# H38R00.net
KiCad netlist of a schematic drawn in EAGLE
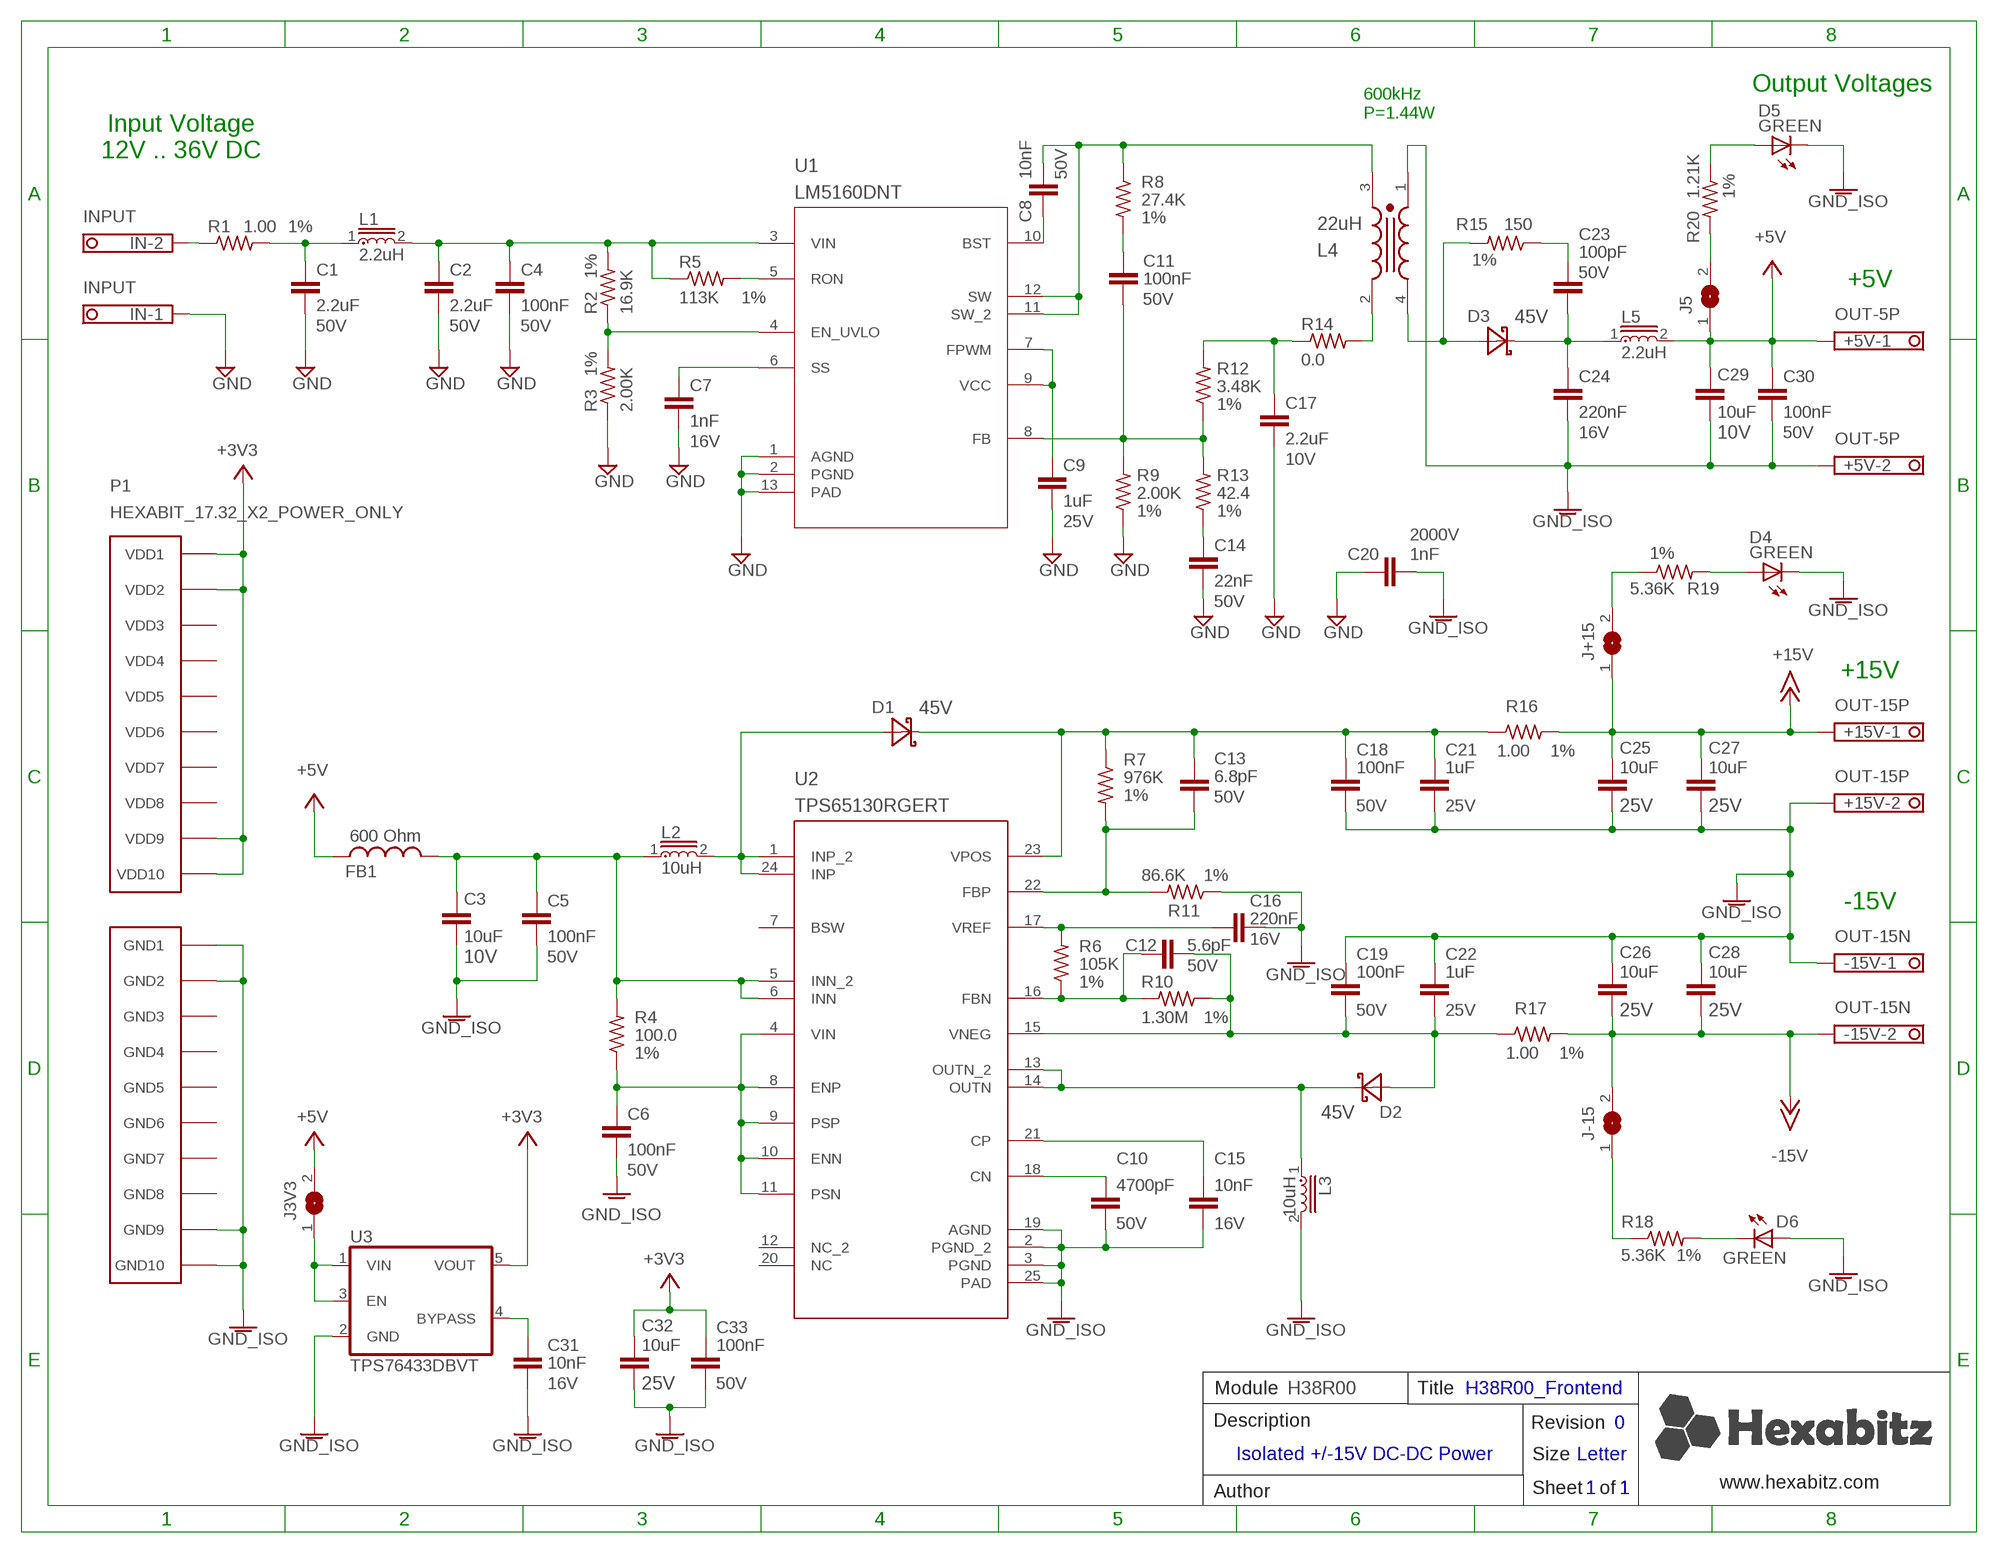
[diagram p0: schematic, sheet 1]

(export (version "E")
  (design (tool "Eeschema 10.0.6"))
  (components
    (comp (ref "+5V")
      (value "OUT-5P")
      (footprint "eagle-import:CON-PHOENIX-350_1751248")
      (fields (field (name "MPN") "1751251"))
      (libsource (lib "eagle-import") (part "CON-PHOENIX-350_1751248"))
    )
    (comp (ref "+15V")
      (value "OUT-15P")
      (footprint "eagle-import:CON-PHOENIX-350_1751248")
      (fields (field (name "MPN") "1751251"))
      (libsource (lib "eagle-import") (part "CON-PHOENIX-350_1751248"))
    )
    (comp (ref "-15V")
      (value "OUT-15N")
      (footprint "eagle-import:CON-PHOENIX-350_1751248")
      (fields (field (name "MPN") "1751251"))
      (libsource (lib "eagle-import") (part "CON-PHOENIX-350_1751248"))
    )
    (comp (ref "C1")
      (value "2.2uF")
      (footprint "eagle-import:C1206K")
      (fields (field (name "MPN") "UMK316B7225KD-T") (field (name "VOLTAGE") "50V"))
      (libsource (lib "eagle-import") (part "C-1206"))
    )
    (comp (ref "C2")
      (value "2.2uF")
      (footprint "eagle-import:C1206K")
      (fields (field (name "MPN") "UMK316B7225KD-T") (field (name "VOLTAGE") "50V"))
      (libsource (lib "eagle-import") (part "C-1206"))
    )
    (comp (ref "C3")
      (value "10uF")
      (footprint "eagle-import:C-0805")
      (fields
        (field (name "CAPACITANCE") "10uF")
        (field (name "MFN") "Würth Elektronik")
        (field (name "MPN") "885012207026")
        (field (name "OCTOPART_URL") "https://octopart.com/885012207026-w%C3%BCrth+elektronik-65419800?r=sp&s=PJ8-ZxRrRL-RXf1D2e7V7w ")
        (field (name "TOLERANCE") "10%")
        (field (name "VOLTAGE_RATING") "10V")
      )
      (libsource (lib "eagle-import") (part "C-0805"))
    )
    (comp (ref "C4")
      (value "100nF")
      (footprint "eagle-import:C-0603")
      (fields
        (field (name "CAPACITANCE") "100nF")
        (field (name "MFN") "TDK")
        (field (name "MPN") "C1608X7R1H104K")
        (field (name "OCTOPART_URL") "https://octopart.com/c1608x7r1h104k080aa-tdk-25947665?r=sp&s=vJ3_28x5RGekN18MBHqpKw")
        (field (name "TOLERANCE") "10%")
        (field (name "VOLTAGE_RATING") "50V")
      )
      (libsource (lib "eagle-import") (part "C-0603"))
    )
    (comp (ref "C5")
      (value "100nF")
      (footprint "eagle-import:C-0603")
      (fields
        (field (name "CAPACITANCE") "100nF")
        (field (name "MFN") "TDK")
        (field (name "MPN") "C1608X7R1H104K")
        (field (name "OCTOPART_URL") "https://octopart.com/c1608x7r1h104k080aa-tdk-25947665?r=sp&s=vJ3_28x5RGekN18MBHqpKw")
        (field (name "TOLERANCE") "10%")
        (field (name "VOLTAGE_RATING") "50V")
      )
      (libsource (lib "eagle-import") (part "C-0603"))
    )
    (comp (ref "C6")
      (value "100nF")
      (footprint "eagle-import:C-0603")
      (fields
        (field (name "CAPACITANCE") "100nF")
        (field (name "MFN") "TDK")
        (field (name "MPN") "C1608X7R1H104K")
        (field (name "OCTOPART_URL") "https://octopart.com/c1608x7r1h104k080aa-tdk-25947665?r=sp&s=vJ3_28x5RGekN18MBHqpKw")
        (field (name "TOLERANCE") "10%")
        (field (name "VOLTAGE_RATING") "50V")
      )
      (libsource (lib "eagle-import") (part "C-0603"))
    )
    (comp (ref "C7")
      (value "1nF")
      (footprint "eagle-import:C-0603")
      (fields
        (field (name "CAPACITANCE") "1nF")
        (field (name "MFN") "Würth Elektronik")
        (field (name "MPN") "885012206034")
        (field (name "OCTOPART_URL") "https://octopart.com/885012206034-w%C3%BCrth+elektronik-53914743?r=sp&s=3y92xzxLSKK6IudBxcGU8w")
        (field (name "TOLERANCE") "10%")
        (field (name "VOLTAGE_RATING") "16V")
      )
      (libsource (lib "eagle-import") (part "C-0603"))
    )
    (comp (ref "C8")
      (value "10nF")
      (footprint "eagle-import:C-0603")
      (fields
        (field (name "CAPACITANCE") "10nF")
        (field (name "MFN") "KEMET")
        (field (name "MPN") "C0603C103J5RACTU")
        (field (name "OCTOPART_URL") "https://octopart.com/c0603c103j5ractu-kemet-91371?r=sp&s=Kyc2xDn-SuWGmNLJldLSIQ")
        (field (name "TOLERANCE") "10%")
        (field (name "VOLTAGE_RATING") "50V")
      )
      (libsource (lib "eagle-import") (part "C-0603"))
    )
    (comp (ref "C9")
      (value "1uF")
      (footprint "eagle-import:C-0603")
      (fields
        (field (name "CAPACITANCE") "1uF")
        (field (name "MFN") "Taiyo Yuden")
        (field (name "MPN") "TMK107B7105KA-T")
        (field (name "OCTOPART_URL") "https://octopart.com/tmk107b7105ka-t-taiyo+yuden-20363789?r=sp&s=C0MvDSixSxq0oU7K_M5ppQ")
        (field (name "TOLERANCE") "10%")
        (field (name "VOLTAGE_RATING") "25V")
      )
      (libsource (lib "eagle-import") (part "C-0603"))
    )
    (comp (ref "C10")
      (value "4700pF")
      (footprint "eagle-import:C-0603")
      (fields
        (field (name "CAPACITANCE") "4700pF")
        (field (name "MFN") "Würth Elektronik")
        (field (name "MPN") "885012206087")
        (field (name "OCTOPART_URL") "https://octopart.com/885012206087-w%C3%BCrth+elektronik-53914796?r=sp&s=1K2nhhCgSUq-KN0bvB69Uw")
        (field (name "TOLERANCE") "10%")
        (field (name "VOLTAGE_RATING") "50V")
      )
      (libsource (lib "eagle-import") (part "C-0603"))
    )
    (comp (ref "C11")
      (value "100nF")
      (footprint "eagle-import:C-0603")
      (fields
        (field (name "CAPACITANCE") "100nF")
        (field (name "MFN") "TDK")
        (field (name "MPN") "C1608X7R1H104K")
        (field (name "OCTOPART_URL") "https://octopart.com/c1608x7r1h104k080aa-tdk-25947665?r=sp&s=vJ3_28x5RGekN18MBHqpKw")
        (field (name "TOLERANCE") "10%")
        (field (name "VOLTAGE_RATING") "50V")
      )
      (libsource (lib "eagle-import") (part "C-0603"))
    )
    (comp (ref "C12")
      (value "5.6pF")
      (footprint "eagle-import:C-0603")
      (fields
        (field (name "CAPACITANCE") "5.6pF")
        (field (name "MFN") "TDK")
        (field (name "MPN") "06035A5R6CAT2A")
        (field (name "OCTOPART_URL") "https://octopart.com/06035a5r6cat2a-avx-194782?r=sp&s=arSRmqwrS2KePu_erVaGmg")
        (field (name "TOLERANCE") "5%")
        (field (name "VOLTAGE_RATING") "50V")
      )
      (libsource (lib "eagle-import") (part "C-0603"))
    )
    (comp (ref "C13")
      (value "6.8pF")
      (footprint "eagle-import:C-0603")
      (fields
        (field (name "CAPACITANCE") "6.8pF")
        (field (name "MFN") "AVX")
        (field (name "MPN") "06035A6R8CAT2A")
        (field (name "OCTOPART_URL") "https://octopart.com/06035a6r8cat2a-avx-194783?r=sp&s=5-5NBtM6RDWLTSW9K30eVg")
        (field (name "TOLERANCE") "10%")
        (field (name "VOLTAGE_RATING") "50V")
      )
      (libsource (lib "eagle-import") (part "C-0603"))
    )
    (comp (ref "C14")
      (value "22nF")
      (footprint "eagle-import:C-0603")
      (fields
        (field (name "CAPACITANCE") "22nF")
        (field (name "MFN") "Murata")
        (field (name "MPN") "GRM188R71H223KA01D")
        (field (name "OCTOPART_URL") "https://octopart.com/grm188r71h223ka01d-murata-196232?r=sp&s=t23e6pi9S5yo9EHFMT_EKg")
        (field (name "TOLERANCE") "10%")
        (field (name "VOLTAGE_RATING") "50V")
      )
      (libsource (lib "eagle-import") (part "C-0603"))
    )
    (comp (ref "C15")
      (value "10nF")
      (footprint "eagle-import:C-0603")
      (fields
        (field (name "CAPACITANCE") "10nF")
        (field (name "MFN") "Würth Elektronik")
        (field (name "MPN") "885012206040")
        (field (name "OCTOPART_URL") "https://octopart.com/885012206040-w%C3%BCrth+elektronik-53914749?r=sp&s=G3_ezLbARM2-FohtMFECqg")
        (field (name "TOLERANCE") "10%")
        (field (name "VOLTAGE_RATING") "16V")
      )
      (libsource (lib "eagle-import") (part "C-0603"))
    )
    (comp (ref "C16")
      (value "220nF")
      (footprint "eagle-import:C-0603")
      (fields
        (field (name "CAPACITANCE") "220nF")
        (field (name "MFN") "Würth Elektronik")
        (field (name "MPN") "885012206048")
        (field (name "OCTOPART_URL") "https://octopart.com/885012206048-w%C3%BCrth+elektronik-53914757?r=sp&s=r2jVh1M7TTWSNtdrsMd35A")
        (field (name "TOLERANCE") "10%")
        (field (name "VOLTAGE_RATING") "16V")
      )
      (libsource (lib "eagle-import") (part "C-0603"))
    )
    (comp (ref "C17")
      (value "2.2uF")
      (footprint "eagle-import:C-0603")
      (fields
        (field (name "CAPACITANCE") "2.2uF")
        (field (name "MFN") "Murata")
        (field (name "MPN") "GRM188R71A225KE15D")
        (field (name "OCTOPART_URL") "https://octopart.com/grm188r71a225ke15d-murata-197889?r=sp&s=UhC5vs9xSQGkDEPPXrg6Ig")
        (field (name "TOLERANCE") "10%")
        (field (name "VOLTAGE_RATING") "10V")
      )
      (libsource (lib "eagle-import") (part "C-0603"))
    )
    (comp (ref "C18")
      (value "100nF")
      (footprint "eagle-import:C-0603")
      (fields
        (field (name "CAPACITANCE") "100nF")
        (field (name "MFN") "TDK")
        (field (name "MPN") "C1608X7R1H104K")
        (field (name "OCTOPART_URL") "https://octopart.com/c1608x7r1h104k080aa-tdk-25947665?r=sp&s=vJ3_28x5RGekN18MBHqpKw")
        (field (name "TOLERANCE") "10%")
        (field (name "VOLTAGE_RATING") "50V")
      )
      (libsource (lib "eagle-import") (part "C-0603"))
    )
    (comp (ref "C19")
      (value "100nF")
      (footprint "eagle-import:C-0603")
      (fields
        (field (name "CAPACITANCE") "100nF")
        (field (name "MFN") "TDK")
        (field (name "MPN") "C1608X7R1H104K")
        (field (name "OCTOPART_URL") "https://octopart.com/c1608x7r1h104k080aa-tdk-25947665?r=sp&s=vJ3_28x5RGekN18MBHqpKw")
        (field (name "TOLERANCE") "10%")
        (field (name "VOLTAGE_RATING") "50V")
      )
      (libsource (lib "eagle-import") (part "C-0603"))
    )
    (comp (ref "C20")
      (value "1nF")
      (footprint "eagle-import:C1206K")
      (fields (field (name "MPN") "202R18W102KV4E") (field (name "VOLTAGE") "2000V"))
      (libsource (lib "eagle-import") (part "C-1206"))
    )
    (comp (ref "C21")
      (value "1uF")
      (footprint "eagle-import:C-0603")
      (fields
        (field (name "CAPACITANCE") "1uF")
        (field (name "MFN") "Taiyo Yuden")
        (field (name "MPN") "TMK107B7105KA-T")
        (field (name "OCTOPART_URL") "https://octopart.com/tmk107b7105ka-t-taiyo+yuden-20363789?r=sp&s=C0MvDSixSxq0oU7K_M5ppQ")
        (field (name "TOLERANCE") "10%")
        (field (name "VOLTAGE_RATING") "25V")
      )
      (libsource (lib "eagle-import") (part "C-0603"))
    )
    (comp (ref "C22")
      (value "1uF")
      (footprint "eagle-import:C-0603")
      (fields
        (field (name "CAPACITANCE") "1uF")
        (field (name "MFN") "Taiyo Yuden")
        (field (name "MPN") "TMK107B7105KA-T")
        (field (name "OCTOPART_URL") "https://octopart.com/tmk107b7105ka-t-taiyo+yuden-20363789?r=sp&s=C0MvDSixSxq0oU7K_M5ppQ")
        (field (name "TOLERANCE") "10%")
        (field (name "VOLTAGE_RATING") "25V")
      )
      (libsource (lib "eagle-import") (part "C-0603"))
    )
    (comp (ref "C23")
      (value "100pF")
      (footprint "eagle-import:C-0603")
      (fields
        (field (name "CAPACITANCE") "100pF")
        (field (name "MFN") "KEMET")
        (field (name "MPN") "C0603C101J5GACTU")
        (field (name "OCTOPART_URL") "https://octopart.com/c0603c101j5gactu-kemet-100052?r=sp&s=G9Wafbc2Rs-t41DcITu08w")
        (field (name "TOLERANCE") "5%")
        (field (name "VOLTAGE_RATING") "50V")
      )
      (libsource (lib "eagle-import") (part "C-0603"))
    )
    (comp (ref "C24")
      (value "220nF")
      (footprint "eagle-import:C-0603")
      (fields
        (field (name "CAPACITANCE") "220nF")
        (field (name "MFN") "Würth Elektronik")
        (field (name "MPN") "885012206048")
        (field (name "OCTOPART_URL") "https://octopart.com/885012206048-w%C3%BCrth+elektronik-53914757?r=sp&s=r2jVh1M7TTWSNtdrsMd35A")
        (field (name "TOLERANCE") "10%")
        (field (name "VOLTAGE_RATING") "16V")
      )
      (libsource (lib "eagle-import") (part "C-0603"))
    )
    (comp (ref "C25")
      (value "10uF")
      (footprint "eagle-import:C-0805")
      (fields
        (field (name "CAPACITANCE") "10uF")
        (field (name "MFN") "Murata")
        (field (name "MPN") "GRM21BC71E106KE11L")
        (field (name "OCTOPART_URL") "https://octopart.com/grm21bc71e106ke11l-murata-51454492?r=sp&s=2Vde2RpCRyqy5YYMvYke3Q ")
        (field (name "TOLERANCE") "10%")
        (field (name "VOLTAGE_RATING") "25V")
      )
      (libsource (lib "eagle-import") (part "C-0805"))
    )
    (comp (ref "C26")
      (value "10uF")
      (footprint "eagle-import:C-0805")
      (fields
        (field (name "CAPACITANCE") "10uF")
        (field (name "MFN") "Murata")
        (field (name "MPN") "GRM21BC71E106KE11L")
        (field (name "OCTOPART_URL") "https://octopart.com/grm21bc71e106ke11l-murata-51454492?r=sp&s=2Vde2RpCRyqy5YYMvYke3Q ")
        (field (name "TOLERANCE") "10%")
        (field (name "VOLTAGE_RATING") "25V")
      )
      (libsource (lib "eagle-import") (part "C-0805"))
    )
    (comp (ref "C27")
      (value "10uF")
      (footprint "eagle-import:C-0805")
      (fields
        (field (name "CAPACITANCE") "10uF")
        (field (name "MFN") "Murata")
        (field (name "MPN") "GRM21BC71E106KE11L")
        (field (name "OCTOPART_URL") "https://octopart.com/grm21bc71e106ke11l-murata-51454492?r=sp&s=2Vde2RpCRyqy5YYMvYke3Q ")
        (field (name "TOLERANCE") "10%")
        (field (name "VOLTAGE_RATING") "25V")
      )
      (libsource (lib "eagle-import") (part "C-0805"))
    )
    (comp (ref "C28")
      (value "10uF")
      (footprint "eagle-import:C-0805")
      (fields
        (field (name "CAPACITANCE") "10uF")
        (field (name "MFN") "Murata")
        (field (name "MPN") "GRM21BC71E106KE11L")
        (field (name "OCTOPART_URL") "https://octopart.com/grm21bc71e106ke11l-murata-51454492?r=sp&s=2Vde2RpCRyqy5YYMvYke3Q")
        (field (name "TOLERANCE") "10%")
        (field (name "VOLTAGE_RATING") "25V")
      )
      (libsource (lib "eagle-import") (part "C-0805"))
    )
    (comp (ref "C29")
      (value "10uF")
      (footprint "eagle-import:C-0805")
      (fields
        (field (name "CAPACITANCE") "10uF")
        (field (name "MFN") "Würth Elektronik")
        (field (name "MPN") "885012207026")
        (field (name "OCTOPART_URL") "https://octopart.com/885012207026-w%C3%BCrth+elektronik-65419800?r=sp&s=PJ8-ZxRrRL-RXf1D2e7V7w")
        (field (name "TOLERANCE") "10%")
        (field (name "VOLTAGE_RATING") "10V")
      )
      (libsource (lib "eagle-import") (part "C-0805"))
    )
    (comp (ref "C30")
      (value "100nF")
      (footprint "eagle-import:C-0603")
      (fields
        (field (name "CAPACITANCE") "100nF")
        (field (name "MFN") "TDK")
        (field (name "MPN") "C1608X7R1H104K")
        (field (name "OCTOPART_URL") "https://octopart.com/c1608x7r1h104k080aa-tdk-25947665?r=sp&s=vJ3_28x5RGekN18MBHqpKw")
        (field (name "TOLERANCE") "10%")
        (field (name "VOLTAGE_RATING") "50V")
      )
      (libsource (lib "eagle-import") (part "C-0603"))
    )
    (comp (ref "C31")
      (value "10nF")
      (footprint "eagle-import:C-0603")
      (fields
        (field (name "CAPACITANCE") "10nF")
        (field (name "MFN") "Würth Elektronik")
        (field (name "MPN") "885012206040")
        (field (name "OCTOPART_URL") "https://octopart.com/885012206040-w%C3%BCrth+elektronik-53914749?r=sp&s=G3_ezLbARM2-FohtMFECqg")
        (field (name "TOLERANCE") "10%")
        (field (name "VOLTAGE_RATING") "16V")
      )
      (libsource (lib "eagle-import") (part "C-0603"))
    )
    (comp (ref "C32")
      (value "10uF")
      (footprint "eagle-import:C-0805")
      (fields
        (field (name "CAPACITANCE") "10uF")
        (field (name "MFN") "Murata")
        (field (name "MPN") "GRM21BC71E106KE11L")
        (field (name "OCTOPART_URL") "https://octopart.com/grm21bc71e106ke11l-murata-51454492?r=sp&s=2Vde2RpCRyqy5YYMvYke3Q")
        (field (name "TOLERANCE") "10%")
        (field (name "VOLTAGE_RATING") "25V")
      )
      (libsource (lib "eagle-import") (part "C-0805"))
    )
    (comp (ref "C33")
      (value "100nF")
      (footprint "eagle-import:C-0603")
      (fields
        (field (name "CAPACITANCE") "100nF")
        (field (name "MFN") "TDK")
        (field (name "MPN") "C1608X7R1H104K")
        (field (name "OCTOPART_URL") "https://octopart.com/c1608x7r1h104k080aa-tdk-25947665?r=sp&s=vJ3_28x5RGekN18MBHqpKw")
        (field (name "TOLERANCE") "10%")
        (field (name "VOLTAGE_RATING") "50V")
      )
      (libsource (lib "eagle-import") (part "C-0603"))
    )
    (comp (ref "D1")
      (value "DIOD-SOD-123")
      (footprint "eagle-import:SOD123")
      (fields
        (field (name "MFN") "ON Semiconductor")
        (field (name "MPN") "NTS245SFT1G")
        (field (name "OCTOPART_URL") "https://octopart.com/nts245sft1g-on+semiconductor-53638116?r=sp&s=Zo8Z59f0QcynsgZ2PtBRwg")
        (field (name "VOLTAGE_RATING_DC") "45V")
      )
      (libsource (lib "eagle-import") (part "DIOD-SOD-123"))
    )
    (comp (ref "D2")
      (value "DIOD-SOD-123")
      (footprint "eagle-import:SOD123")
      (fields
        (field (name "MFN") "ON Semiconductor")
        (field (name "MPN") "NTS245SFT1G")
        (field (name "OCTOPART_URL") "https://octopart.com/nts245sft1g-on+semiconductor-53638116?r=sp&s=Zo8Z59f0QcynsgZ2PtBRwg")
        (field (name "VOLTAGE_RATING_DC") "45V")
      )
      (libsource (lib "eagle-import") (part "DIOD-SOD-123"))
    )
    (comp (ref "D3")
      (value "DIOD-SOD-123")
      (footprint "eagle-import:SOD123")
      (fields
        (field (name "MFN") "ON Semiconductor")
        (field (name "MPN") "NTS245SFT1G")
        (field (name "OCTOPART_URL") "https://octopart.com/nts245sft1g-on+semiconductor-53638116?r=sp&s=Zo8Z59f0QcynsgZ2PtBRwg")
        (field (name "VOLTAGE_RATING_DC") "45V")
      )
      (libsource (lib "eagle-import") (part "DIOD-SOD-123"))
    )
    (comp (ref "D4")
      (value "GREEN")
      (footprint "eagle-import:VLMS1300-GS08")
      (fields (field (name "MPN") "VLMTG1300-GS08"))
      (libsource (lib "eagle-import") (part "VLMTG1300-GS08"))
    )
    (comp (ref "D5")
      (value "GREEN")
      (footprint "eagle-import:VLMS1300-GS08")
      (fields (field (name "MPN") "VLMTG1300-GS08"))
      (libsource (lib "eagle-import") (part "VLMTG1300-GS08"))
    )
    (comp (ref "D6")
      (value "GREEN")
      (footprint "eagle-import:VLMS1300-GS08")
      (fields (field (name "MPN") "VLMTG1300-GS08"))
      (libsource (lib "eagle-import") (part "VLMTG1300-GS08"))
    )
    (comp (ref "FB1")
      (value "600 Ohm")
      (footprint "eagle-import:FB-0603")
      (fields
        (field (name "MFN") "Murata")
        (field (name "MPN") "BLM18KG601SN1D")
        (field (name "OCTOPART_URL") "https://octopart.com/blm18kg601sn1d-murata-12276433?r=sp&s=hc41AUOpRWisdZqqWWZOxA")
      )
      (libsource (lib "eagle-import") (part "FB-0603"))
    )
    (comp (ref "IN")
      (value "INPUT")
      (footprint "eagle-import:CON-PHOENIX-350_1751248")
      (fields (field (name "MPN") "1751251"))
      (libsource (lib "eagle-import") (part "CON-PHOENIX-350_1751248"))
    )
    (comp (ref "J+15")
      (value "SJ")
      (footprint "eagle-import:SJ")
      (libsource (lib "eagle-import") (part "SJ"))
    )
    (comp (ref "J-15")
      (value "SJ")
      (footprint "eagle-import:SJ")
      (libsource (lib "eagle-import") (part "SJ"))
    )
    (comp (ref "J3V3")
      (value "SJ")
      (footprint "eagle-import:SJ")
      (libsource (lib "eagle-import") (part "SJ"))
    )
    (comp (ref "J5") (value "SJ") (footprint "eagle-import:SJ") (libsource (lib "eagle-import") (part "SJ")))
    (comp (ref "L1")
      (value "2.2uH")
      (footprint "eagle-import:C-0603")
      (fields (field (name "MPN") "LQM18PN2R2MFHD"))
      (libsource (lib "eagle-import") (part "LQM18PN2R2MFHD"))
    )
    (comp (ref "L2")
      (value "10uH")
      (footprint "eagle-import:WUERTH_ELEKTRONIK_74404024100_0")
      (fields (field (name "MF") "Wuerth Elektronik") (field (name "MPN") "74404024100"))
      (libsource (lib "eagle-import") (part "WUERTH_ELEKTRONIK_74404024100WUERTH_ELEKTRONIK_74404024100_0_0"))
    )
    (comp (ref "L3")
      (value "10uH")
      (footprint "eagle-import:WUERTH_ELEKTRONIK_74404024100_0")
      (fields (field (name "MF") "Wuerth Elektronik") (field (name "MPN") "74404024100"))
      (libsource (lib "eagle-import") (part "WUERTH_ELEKTRONIK_74404024100WUERTH_ELEKTRONIK_74404024100_0_0"))
    )
    (comp (ref "L4")
      (value "22uH")
      (footprint "eagle-import:WUERTH_ELEKTRONIK_74489430220_0")
      (fields (field (name "MF") "Wuerth Elektronik") (field (name "MPN") "74489430220"))
      (libsource (lib "eagle-import") (part "WUERTH_ELEKTRONIK_74489430220WUERTH_ELEKTRONIK_74489430220_0_0"))
    )
    (comp (ref "L5")
      (value "2.2uH")
      (footprint "eagle-import:C-0603")
      (fields (field (name "MPN") "LQM18PN2R2MFHD"))
      (libsource (lib "eagle-import") (part "LQM18PN2R2MFHD"))
    )
    (comp (ref "P1")
      (value "HEXABIT_17.32_X2_POWER_ONLY")
      (footprint "eagle-import:HEXABIT_17.32_X2_POWER_ONLY")
      (libsource (lib "eagle-import") (part "HEXABIT_?_X2_POWER_ONLY17.32"))
    )
    (comp (ref "R1")
      (value "1.00")
      (footprint "eagle-import:R-0603")
      (fields
        (field (name "MFN") "Vishay-Dale")
        (field (name "MPN") "CRCW06031R00FKEA")
        (field (name "OCTOPART_URL") "https://octopart.com/crcw06031r00fkea-vishay-39713722?r=sp&s=biXSlGylTBiwPOCcABx_kA")
        (field (name "RESISTANCE") "1.00")
        (field (name "TOLERANCE") "1%")
      )
      (libsource (lib "eagle-import") (part "R-0603"))
    )
    (comp (ref "R2")
      (value "16.9K")
      (footprint "eagle-import:R-0603")
      (fields
        (field (name "MFN") "Vishay")
        (field (name "MPN") "CRCW060316K9FKEA")
        (field (name "OCTOPART_URL") "https://octopart.com/crcw060316k9fkea-vishay-39809405?r=sp&s=gpyoC5sESS275Bx1L_ovfA")
        (field (name "RESISTANCE") "16.9K")
        (field (name "TOLERANCE") "1%")
      )
      (libsource (lib "eagle-import") (part "R-0603"))
    )
    (comp (ref "R3")
      (value "2.00K")
      (footprint "eagle-import:R-0603")
      (fields
        (field (name "MFN") "Vishay")
        (field (name "MPN") "CRCW06032K00FKEA")
        (field (name "OCTOPART_URL") "https://octopart.com/crcw06032k00fkea-vishay-39455515?r=sp&s=oLMBsKnqSyiGxb37P4YGRQ")
        (field (name "RESISTANCE") "2.00k")
        (field (name "TOLERANCE") "1%")
      )
      (libsource (lib "eagle-import") (part "R-0603"))
    )
    (comp (ref "R4")
      (value "100.0")
      (footprint "eagle-import:R-0603")
      (fields
        (field (name "MFN") "Vishay")
        (field (name "MPN") "CRCW0603100RFKEA")
        (field (name "OCTOPART_URL") "https://octopart.com/crcw0603100rfkea-vishay-39454046?r=sp&s=ZCLXy-8WTNaYdj0NMUzO0A")
        (field (name "RESISTANCE") "100.0")
        (field (name "TOLERANCE") "1%")
      )
      (libsource (lib "eagle-import") (part "R-0603"))
    )
    (comp (ref "R5")
      (value "113K")
      (footprint "eagle-import:R-0603")
      (fields
        (field (name "MFN") "Vishay")
        (field (name "MPN") "CRCW0603113KFKEA")
        (field (name "OCTOPART_URL") "https://octopart.com/crcw0603113kfkea-vishay-39817257?r=sp&s=CTaWAi24RJSm7_6d5HDAcw")
        (field (name "RESISTANCE") "113K")
        (field (name "TOLERANCE") "1%")
      )
      (libsource (lib "eagle-import") (part "R-0603"))
    )
    (comp (ref "R6")
      (value "105K")
      (footprint "eagle-import:R-0603")
      (fields
        (field (name "MFN") "Vishay")
        (field (name "MPN") "CRCW0603105KFKEA")
        (field (name "OCTOPART_URL") "https://octopart.com/crcw0603105kfkea-vishay-39783419?r=sp&s=m57LqOW9SZi8auMTWgZAuA")
        (field (name "RESISTANCE") "105K")
        (field (name "TOLERANCE") "1%")
      )
      (libsource (lib "eagle-import") (part "R-0603"))
    )
    (comp (ref "R7")
      (value "976K")
      (footprint "eagle-import:R-0603")
      (fields
        (field (name "MFN") "Vishay")
        (field (name "MPN") "CRCW0603976KFKEA")
        (field (name "OCTOPART_URL") "https://octopart.com/crcw0603976kfkea-vishay-39847458?r=sp&s=cUxC9lyxRzee74EppCoygA")
        (field (name "RESISTANCE") "976K")
        (field (name "TOLERANCE") "1%")
      )
      (libsource (lib "eagle-import") (part "R-0603"))
    )
    (comp (ref "R8")
      (value "27.4K")
      (footprint "eagle-import:R-0603")
      (fields
        (field (name "MFN") "Vishay")
        (field (name "MPN") "CRCW060327K4FKEA")
        (field (name "OCTOPART_URL") "https://octopart.com/crcw060327k4fkea-vishay-40950191?r=sp&s=-sh_flwyTnabpVfO2SO3MQ")
        (field (name "RESISTANCE") "27.4K")
        (field (name "TOLERANCE") "1%")
      )
      (libsource (lib "eagle-import") (part "R-0603"))
    )
    (comp (ref "R9")
      (value "2.00K")
      (footprint "eagle-import:R-0603")
      (fields
        (field (name "MFN") "Vishay")
        (field (name "MPN") "CRCW06032K00FKEA")
        (field (name "OCTOPART_URL") "https://octopart.com/crcw06032k00fkea-vishay-39455515?r=sp&s=oLMBsKnqSyiGxb37P4YGRQ")
        (field (name "RESISTANCE") "2.00k")
        (field (name "TOLERANCE") "1%")
      )
      (libsource (lib "eagle-import") (part "R-0603"))
    )
    (comp (ref "R10")
      (value "1.30M")
      (footprint "eagle-import:R-0603")
      (fields
        (field (name "MFN") "Vishay")
        (field (name "MPN") "CRCW06031M30FKEA")
        (field (name "OCTOPART_URL") "https://octopart.com/crcw06031m30fkea-vishay-39601140?r=sp&s=IFmbrVO2QdmVcSmXO7E1AA")
        (field (name "RESISTANCE") "1.30M")
        (field (name "TOLERANCE") "1%")
      )
      (libsource (lib "eagle-import") (part "R-0603"))
    )
    (comp (ref "R11")
      (value "86.6K")
      (footprint "eagle-import:R-0603")
      (fields
        (field (name "MFN") "Vishay")
        (field (name "MPN") "CRCW060386K6FKEA")
        (field (name "OCTOPART_URL") "https://octopart.com/crcw060386k6fkea-vishay-39809057?r=sp&s=kiKKot43Sa6nkjOnoApb7Q")
        (field (name "RESISTANCE") "86.6K")
        (field (name "TOLERANCE") "1%")
      )
      (libsource (lib "eagle-import") (part "R-0603"))
    )
    (comp (ref "R12")
      (value "3.48K")
      (footprint "eagle-import:R-0603")
      (fields
        (field (name "MFN") "Vishay")
        (field (name "MPN") "CRCW06033K48FKEA")
        (field (name "OCTOPART_URL") "https://octopart.com/crcw06033k48fkea-vishay-39806638?r=sp&s=N5g7S2AyTDmMWBX-_wGc6Q")
        (field (name "RESISTANCE") "3.48K")
        (field (name "TOLERANCE") "1%")
      )
      (libsource (lib "eagle-import") (part "R-0603"))
    )
    (comp (ref "R13")
      (value "42.4")
      (footprint "eagle-import:R-0603")
      (fields
        (field (name "MFN") "Vishay")
        (field (name "MPN") "CRCW060342R2FKEA")
        (field (name "OCTOPART_URL") "https://octopart.com/crcw060342r2fkea-vishay-39808977?r=sp&s=-XoBdwS-TmODK1i1WGs3Gw")
        (field (name "RESISTANCE") "42.2R")
        (field (name "TOLERANCE") "1%")
      )
      (libsource (lib "eagle-import") (part "R-0603"))
    )
    (comp (ref "R14")
      (value "0.0")
      (footprint "eagle-import:R-0603")
      (fields
        (field (name "MFN") "Panasonic")
        (field (name "MPN") "ERJ-3GEY0R00V")
        (field (name "OCTOPART_URL") "https://octopart.com/erj-3gey0r00v-panasonic-55389238?r=sp&s=8dmrTZyCS32IAujh55Hh-g")
        (field (name "RESISTANCE") "0.0R")
        (field (name "TOLERANCE") "5%")
      )
      (libsource (lib "eagle-import") (part "R-0603"))
    )
    (comp (ref "R15")
      (value "150")
      (footprint "eagle-import:R-0603")
      (fields
        (field (name "MFN") "Vishay")
        (field (name "MPN") "CRCW0603150RFKEA")
        (field (name "OCTOPART_URL") "https://octopart.com/crcw0603150rfkea-vishay-39455211?r=sp&s=fhZ4fTqDSW-fVK_X4mehlA")
        (field (name "RESISTANCE") "150R")
        (field (name "TOLERANCE") "1%")
      )
      (libsource (lib "eagle-import") (part "R-0603"))
    )
    (comp (ref "R16")
      (value "1.00")
      (footprint "eagle-import:R-0603")
      (fields
        (field (name "MFN") "Vishay-Dale")
        (field (name "MPN") "CRCW06031R00FKEA")
        (field (name "OCTOPART_URL") "https://octopart.com/crcw06031r00fkea-vishay-39713722?r=sp&s=biXSlGylTBiwPOCcABx_kA")
        (field (name "RESISTANCE") "1.00")
        (field (name "TOLERANCE") "1%")
      )
      (libsource (lib "eagle-import") (part "R-0603"))
    )
    (comp (ref "R17")
      (value "1.00")
      (footprint "eagle-import:R-0603")
      (fields
        (field (name "MFN") "Vishay-Dale")
        (field (name "MPN") "CRCW06031R00FKEA")
        (field (name "OCTOPART_URL") "https://octopart.com/crcw06031r00fkea-vishay-39713722?r=sp&s=biXSlGylTBiwPOCcABx_kA")
        (field (name "RESISTANCE") "1.00")
        (field (name "TOLERANCE") "1%")
      )
      (libsource (lib "eagle-import") (part "R-0603"))
    )
    (comp (ref "R18")
      (value "5.36K")
      (footprint "eagle-import:R-0603")
      (fields
        (field (name "MFN") "Vishay")
        (field (name "MPN") "CRCW06035K36FKEA")
        (field (name "OCTOPART_URL") "https://octopart.com/crcw06035k36fkea-vishay-39850082?r=sp&s=UzQdyXKeQlK-zUZHNwTiSQ")
        (field (name "RESISTANCE") "5.36K")
        (field (name "TOLERANCE") "1%")
      )
      (libsource (lib "eagle-import") (part "R-0603"))
    )
    (comp (ref "R19")
      (value "5.36K")
      (footprint "eagle-import:R-0603")
      (fields
        (field (name "MFN") "Vishay")
        (field (name "MPN") "CRCW06035K36FKEA")
        (field (name "OCTOPART_URL") "https://octopart.com/crcw06035k36fkea-vishay-39850082?r=sp&s=UzQdyXKeQlK-zUZHNwTiSQ")
        (field (name "RESISTANCE") "5.36K")
        (field (name "TOLERANCE") "1%")
      )
      (libsource (lib "eagle-import") (part "R-0603"))
    )
    (comp (ref "R20")
      (value "1.21K")
      (footprint "eagle-import:R-0603")
      (fields
        (field (name "MFN") "Vishay")
        (field (name "MPN") "CRCW06031K21FKEA")
        (field (name "OCTOPART_URL") "https://octopart.com/crcw06031k21fkea-vishay-39455541?r=sp&s=DmmN7huOS0CziwVau3vt0g")
        (field (name "RESISTANCE") "1.21K")
        (field (name "TOLERANCE") "1%")
      )
      (libsource (lib "eagle-import") (part "R-0603"))
    )
    (comp (ref "U1")
      (value "LM5160DNT")
      (footprint "eagle-import:DNT0012B")
      (fields (field (name "MANUFACTURER") "Texas Instruments"))
      (libsource (lib "eagle-import") (part "LM5160DNT"))
    )
    (comp (ref "U2")
      (value "TPS65130RGERT")
      (footprint "eagle-import:RGE0024B_NV")
      (fields
        (field (name "ALTERNATE_PARTNUMBER") "TPS65130RGET")
        (field (name "MANUFACTURER") "Texas Instruments")
        (field (name "PARTNUMBER") "TPS65130RGER")
      )
      (libsource (lib "eagle-import") (part "TPS65130RGERT"))
    )
    (comp (ref "U3")
      (value "TPS76433DBVT")
      (footprint "eagle-import:SOT25")
      (libsource (lib "eagle-import") (part "TPS764DBVT33"))
    )
  )
  (nets
    (net (code "1") (name "+3V3") (class "Default")
      (node (ref "C32") (pin "1") (pinfunction "1_1") (pintype "passive"))
      (node (ref "C33") (pin "1") (pinfunction "1_1") (pintype "passive"))
      (node (ref "P1") (pin "PAD_PU11") (pinfunction "VDD1_PAD_PU11") (pintype "power_in"))
      (node (ref "P1") (pin "PAD_PU12") (pinfunction "VDD2_PAD_PU12") (pintype "power_in"))
      (node (ref "P1") (pin "PAD_PU19") (pinfunction "VDD9_PAD_PU19") (pintype "power_in"))
      (node (ref "P1") (pin "PAD_PU20") (pinfunction "VDD10_PAD_PU20") (pintype "power_in"))
      (node (ref "U3") (pin "5") (pinfunction "VOUT_5") (pintype "passive"))
    )
    (net (code "2") (name "+5V") (class "Default")
      (node (ref "+5V") (pin "1") (pinfunction "K_1") (pintype "passive"))
      (node (ref "C29") (pin "1") (pinfunction "1_1") (pintype "passive"))
      (node (ref "C30") (pin "1") (pinfunction "1_1") (pintype "passive"))
      (node (ref "FB1") (pin "1") (pinfunction "1_1") (pintype "passive"))
      (node (ref "J3V3") (pin "2") (pinfunction "2_2") (pintype "passive"))
      (node (ref "J5") (pin "1") (pinfunction "1_1") (pintype "passive"))
      (node (ref "L5") (pin "2") (pinfunction "2_2") (pintype "passive"))
    )
    (net (code "3") (name "+15V") (class "Default")
      (node (ref "+15V") (pin "1") (pinfunction "K_1") (pintype "passive"))
      (node (ref "C25") (pin "1") (pinfunction "1_1") (pintype "passive"))
      (node (ref "C27") (pin "1") (pinfunction "1_1") (pintype "passive"))
      (node (ref "J+15") (pin "1") (pinfunction "1_1") (pintype "passive"))
      (node (ref "R16") (pin "2") (pinfunction "2_2") (pintype "passive"))
    )
    (net (code "4") (name "-15V") (class "Default")
      (node (ref "-15V") (pin "2") (pinfunction "K_2") (pintype "passive"))
      (node (ref "C26") (pin "2") (pinfunction "2_2") (pintype "passive"))
      (node (ref "C28") (pin "2") (pinfunction "2_2") (pintype "passive"))
      (node (ref "J-15") (pin "2") (pinfunction "2_2") (pintype "passive"))
      (node (ref "R17") (pin "2") (pinfunction "2_2") (pintype "passive"))
    )
    (net (code "5") (name "/GND3") (class "Default")
      (node (ref "P1") (pin "PAD_PD13") (pinfunction "GND3_PAD_PD13") (pintype "power_in"))
    )
    (net (code "6") (name "/GND4") (class "Default")
      (node (ref "P1") (pin "PAD_PD14") (pinfunction "GND4_PAD_PD14") (pintype "power_in"))
    )
    (net (code "7") (name "/GND5") (class "Default")
      (node (ref "P1") (pin "PAD_PD15") (pinfunction "GND5_PAD_PD15") (pintype "power_in"))
    )
    (net (code "8") (name "/GND6") (class "Default")
      (node (ref "P1") (pin "PAD_PD16") (pinfunction "GND6_PAD_PD16") (pintype "power_in"))
    )
    (net (code "9") (name "/GND7") (class "Default")
      (node (ref "P1") (pin "PAD_PD17") (pinfunction "GND7_PAD_PD17") (pintype "power_in"))
    )
    (net (code "10") (name "/GND8") (class "Default")
      (node (ref "P1") (pin "PAD_PD18") (pinfunction "GND8_PAD_PD18") (pintype "power_in"))
    )
    (net (code "11") (name "/VDD3") (class "Default")
      (node (ref "P1") (pin "PAD_PU13") (pinfunction "VDD3_PAD_PU13") (pintype "power_in"))
    )
    (net (code "12") (name "/VDD4") (class "Default")
      (node (ref "P1") (pin "PAD_PU14") (pinfunction "VDD4_PAD_PU14") (pintype "power_in"))
    )
    (net (code "13") (name "/VDD5") (class "Default")
      (node (ref "P1") (pin "PAD_PU15") (pinfunction "VDD5_PAD_PU15") (pintype "power_in"))
    )
    (net (code "14") (name "/VDD6") (class "Default")
      (node (ref "P1") (pin "PAD_PU16") (pinfunction "VDD6_PAD_PU16") (pintype "power_in"))
    )
    (net (code "15") (name "/VDD7") (class "Default")
      (node (ref "P1") (pin "PAD_PU17") (pinfunction "VDD7_PAD_PU17") (pintype "power_in"))
    )
    (net (code "16") (name "/VDD8") (class "Default")
      (node (ref "P1") (pin "PAD_PU18") (pinfunction "VDD8_PAD_PU18") (pintype "power_in"))
    )
    (net (code "17") (name "GND") (class "Default")
      (node (ref "C1") (pin "2") (pinfunction "2_2") (pintype "passive"))
      (node (ref "C14") (pin "2") (pinfunction "2_2") (pintype "passive"))
      (node (ref "C17") (pin "2") (pinfunction "2_2") (pintype "passive"))
      (node (ref "C2") (pin "2") (pinfunction "2_2") (pintype "passive"))
      (node (ref "C20") (pin "1") (pinfunction "1_1") (pintype "passive"))
      (node (ref "C4") (pin "2") (pinfunction "2_2") (pintype "passive"))
      (node (ref "C7") (pin "2") (pinfunction "2_2") (pintype "passive"))
      (node (ref "C9") (pin "2") (pinfunction "2_2") (pintype "passive"))
      (node (ref "IN") (pin "1") (pinfunction "K_1") (pintype "passive"))
      (node (ref "R3") (pin "1") (pinfunction "1_1") (pintype "passive"))
      (node (ref "R9") (pin "1") (pinfunction "1_1") (pintype "passive"))
      (node (ref "U1") (pin "1") (pinfunction "AGND_1") (pintype "power_in"))
      (node (ref "U1") (pin "13") (pinfunction "PAD_13") (pintype "power_in"))
      (node (ref "U1") (pin "2") (pinfunction "PGND_2") (pintype "power_in"))
    )
    (net (code "18") (name "GND_ISO") (class "Default")
      (node (ref "+15V") (pin "2") (pinfunction "K_2") (pintype "passive"))
      (node (ref "+5V") (pin "2") (pinfunction "K_2") (pintype "passive"))
      (node (ref "-15V") (pin "1") (pinfunction "K_1") (pintype "passive"))
      (node (ref "C10") (pin "2") (pinfunction "2_2") (pintype "passive"))
      (node (ref "C15") (pin "2") (pinfunction "2_2") (pintype "passive"))
      (node (ref "C16") (pin "2") (pinfunction "2_2") (pintype "passive"))
      (node (ref "C18") (pin "2") (pinfunction "2_2") (pintype "passive"))
      (node (ref "C19") (pin "1") (pinfunction "1_1") (pintype "passive"))
      (node (ref "C20") (pin "2") (pinfunction "2_2") (pintype "passive"))
      (node (ref "C21") (pin "2") (pinfunction "2_2") (pintype "passive"))
      (node (ref "C22") (pin "1") (pinfunction "1_1") (pintype "passive"))
      (node (ref "C24") (pin "2") (pinfunction "2_2") (pintype "passive"))
      (node (ref "C25") (pin "2") (pinfunction "2_2") (pintype "passive"))
      (node (ref "C26") (pin "1") (pinfunction "1_1") (pintype "passive"))
      (node (ref "C27") (pin "2") (pinfunction "2_2") (pintype "passive"))
      (node (ref "C28") (pin "1") (pinfunction "1_1") (pintype "passive"))
      (node (ref "C29") (pin "2") (pinfunction "2_2") (pintype "passive"))
      (node (ref "C3") (pin "2") (pinfunction "2_2") (pintype "passive"))
      (node (ref "C30") (pin "2") (pinfunction "2_2") (pintype "passive"))
      (node (ref "C31") (pin "2") (pinfunction "2_2") (pintype "passive"))
      (node (ref "C32") (pin "2") (pinfunction "2_2") (pintype "passive"))
      (node (ref "C33") (pin "2") (pinfunction "2_2") (pintype "passive"))
      (node (ref "C5") (pin "2") (pinfunction "2_2") (pintype "passive"))
      (node (ref "C6") (pin "2") (pinfunction "2_2") (pintype "passive"))
      (node (ref "D4") (pin "C") (pinfunction "C_C") (pintype "passive"))
      (node (ref "D5") (pin "C") (pinfunction "C_C") (pintype "passive"))
      (node (ref "D6") (pin "A") (pinfunction "A_A") (pintype "passive"))
      (node (ref "L3") (pin "2") (pinfunction "2_2") (pintype "passive"))
      (node (ref "L4") (pin "1") (pinfunction "1_1") (pintype "passive"))
      (node (ref "P1") (pin "PAD_PD11") (pinfunction "GND1_PAD_PD11") (pintype "power_in"))
      (node (ref "P1") (pin "PAD_PD12") (pinfunction "GND2_PAD_PD12") (pintype "power_in"))
      (node (ref "P1") (pin "PAD_PD19") (pinfunction "GND9_PAD_PD19") (pintype "power_in"))
      (node (ref "P1") (pin "PAD_PD20") (pinfunction "GND10_PAD_PD20") (pintype "power_in"))
      (node (ref "R11") (pin "1") (pinfunction "1_1") (pintype "passive"))
      (node (ref "U2") (pin "19") (pinfunction "AGND_19") (pintype "power_in"))
      (node (ref "U2") (pin "2") (pinfunction "PGND_2_2") (pintype "power_in"))
      (node (ref "U2") (pin "25") (pinfunction "PAD_25") (pintype "power_in"))
      (node (ref "U2") (pin "3") (pinfunction "PGND_3") (pintype "power_in"))
      (node (ref "U3") (pin "2") (pinfunction "GND_2") (pintype "passive"))
    )
    (net (code "19") (name "Net-(C1-Pad1)") (class "Default")
      (node (ref "C1") (pin "1") (pinfunction "1_1") (pintype "passive"))
      (node (ref "L1") (pin "1") (pinfunction "1_1") (pintype "passive"))
      (node (ref "R1") (pin "2") (pinfunction "2_2") (pintype "passive"))
    )
    (net (code "20") (name "Net-(C11-Pad1)") (class "Default")
      (node (ref "C11") (pin "1") (pinfunction "1_1") (pintype "passive"))
      (node (ref "R8") (pin "2") (pinfunction "2_2") (pintype "passive"))
    )
    (net (code "21") (name "Net-(C14-Pad1)") (class "Default")
      (node (ref "C14") (pin "1") (pinfunction "1_1") (pintype "passive"))
      (node (ref "R13") (pin "1") (pinfunction "1_1") (pintype "passive"))
    )
    (net (code "22") (name "Net-(C17-Pad1)") (class "Default")
      (node (ref "C17") (pin "1") (pinfunction "1_1") (pintype "passive"))
      (node (ref "R12") (pin "2") (pinfunction "2_2") (pintype "passive"))
      (node (ref "R14") (pin "1") (pinfunction "1_1") (pintype "passive"))
    )
    (net (code "23") (name "Net-(C23-Pad1)") (class "Default")
      (node (ref "C23") (pin "1") (pinfunction "1_1") (pintype "passive"))
      (node (ref "R15") (pin "1") (pinfunction "1_1") (pintype "passive"))
    )
    (net (code "24") (name "Net-(D1-A)") (class "Default")
      (node (ref "D1") (pin "1") (pinfunction "A_1") (pintype "passive"))
      (node (ref "L2") (pin "2") (pinfunction "2_2") (pintype "passive"))
      (node (ref "U2") (pin "1") (pinfunction "INP_2_1") (pintype "power_in"))
      (node (ref "U2") (pin "24") (pinfunction "INP_24") (pintype "power_in"))
    )
    (net (code "25") (name "Net-(D1-C)") (class "Default")
      (node (ref "C13") (pin "2") (pinfunction "2_2") (pintype "passive"))
      (node (ref "C18") (pin "1") (pinfunction "1_1") (pintype "passive"))
      (node (ref "C21") (pin "1") (pinfunction "1_1") (pintype "passive"))
      (node (ref "D1") (pin "2") (pinfunction "C_2") (pintype "passive"))
      (node (ref "R16") (pin "1") (pinfunction "1_1") (pintype "passive"))
      (node (ref "R7") (pin "1") (pinfunction "1_1") (pintype "passive"))
      (node (ref "U2") (pin "23") (pinfunction "VPOS_23") (pintype "input"))
    )
    (net (code "26") (name "Net-(D2-A)") (class "Default")
      (node (ref "C12") (pin "2") (pinfunction "2_2") (pintype "passive"))
      (node (ref "C19") (pin "2") (pinfunction "2_2") (pintype "passive"))
      (node (ref "C22") (pin "2") (pinfunction "2_2") (pintype "passive"))
      (node (ref "D2") (pin "1") (pinfunction "A_1") (pintype "passive"))
      (node (ref "R10") (pin "1") (pinfunction "1_1") (pintype "passive"))
      (node (ref "R17") (pin "1") (pinfunction "1_1") (pintype "passive"))
      (node (ref "U2") (pin "15") (pinfunction "VNEG_15") (pintype "input"))
    )
    (net (code "27") (name "Net-(D2-C)") (class "Default")
      (node (ref "D2") (pin "2") (pinfunction "C_2") (pintype "passive"))
      (node (ref "L3") (pin "1") (pinfunction "1_1") (pintype "passive"))
      (node (ref "U2") (pin "13") (pinfunction "OUTN_2_13") (pintype "power_in"))
      (node (ref "U2") (pin "14") (pinfunction "OUTN_14") (pintype "power_in"))
    )
    (net (code "28") (name "Net-(D3-A)") (class "Default")
      (node (ref "D3") (pin "1") (pinfunction "A_1") (pintype "passive"))
      (node (ref "L4") (pin "4") (pinfunction "4_4") (pintype "passive"))
      (node (ref "R15") (pin "2") (pinfunction "2_2") (pintype "passive"))
    )
    (net (code "29") (name "Net-(D3-C)") (class "Default")
      (node (ref "C23") (pin "2") (pinfunction "2_2") (pintype "passive"))
      (node (ref "C24") (pin "1") (pinfunction "1_1") (pintype "passive"))
      (node (ref "D3") (pin "2") (pinfunction "C_2") (pintype "passive"))
      (node (ref "L5") (pin "1") (pinfunction "1_1") (pintype "passive"))
    )
    (net (code "30") (name "Net-(D4-PadA)") (class "Default")
      (node (ref "D4") (pin "A") (pinfunction "A_A") (pintype "passive"))
      (node (ref "R19") (pin "2") (pinfunction "2_2") (pintype "passive"))
    )
    (net (code "31") (name "Net-(D5-PadA)") (class "Default")
      (node (ref "D5") (pin "A") (pinfunction "A_A") (pintype "passive"))
      (node (ref "R20") (pin "1") (pinfunction "1_1") (pintype "passive"))
    )
    (net (code "32") (name "Net-(D6-PadC)") (class "Default")
      (node (ref "D6") (pin "C") (pinfunction "C_C") (pintype "passive"))
      (node (ref "R18") (pin "2") (pinfunction "2_2") (pintype "passive"))
    )
    (net (code "33") (name "Net-(INB-K)") (class "Default")
      (node (ref "IN") (pin "2") (pinfunction "K_2") (pintype "passive"))
      (node (ref "R1") (pin "1") (pinfunction "1_1") (pintype "passive"))
    )
    (net (code "34") (name "Net-(J+15-Pad2)") (class "Default")
      (node (ref "J+15") (pin "2") (pinfunction "2_2") (pintype "passive"))
      (node (ref "R19") (pin "1") (pinfunction "1_1") (pintype "passive"))
    )
    (net (code "35") (name "Net-(J-15-Pad1)") (class "Default")
      (node (ref "J-15") (pin "1") (pinfunction "1_1") (pintype "passive"))
      (node (ref "R18") (pin "1") (pinfunction "1_1") (pintype "passive"))
    )
    (net (code "36") (name "Net-(J5-Pad2)") (class "Default")
      (node (ref "J5") (pin "2") (pinfunction "2_2") (pintype "passive"))
      (node (ref "R20") (pin "2") (pinfunction "2_2") (pintype "passive"))
    )
    (net (code "37") (name "Net-(L4-Pad2)") (class "Default")
      (node (ref "L4") (pin "2") (pinfunction "2_2") (pintype "passive"))
      (node (ref "R14") (pin "2") (pinfunction "2_2") (pintype "passive"))
    )
    (net (code "38") (name "Net-(U1-BST)") (class "Default")
      (node (ref "C8") (pin "1") (pinfunction "1_1") (pintype "passive"))
      (node (ref "U1") (pin "10") (pinfunction "BST_10") (pintype "power_in"))
    )
    (net (code "39") (name "Net-(U1-EN_UVLO)") (class "Default")
      (node (ref "R2") (pin "1") (pinfunction "1_1") (pintype "passive"))
      (node (ref "R3") (pin "2") (pinfunction "2_2") (pintype "passive"))
      (node (ref "U1") (pin "4") (pinfunction "EN_UVLO_4") (pintype "input"))
    )
    (net (code "40") (name "Net-(U1-FB)") (class "Default")
      (node (ref "C11") (pin "2") (pinfunction "2_2") (pintype "passive"))
      (node (ref "R12") (pin "1") (pinfunction "1_1") (pintype "passive"))
      (node (ref "R13") (pin "2") (pinfunction "2_2") (pintype "passive"))
      (node (ref "R9") (pin "2") (pinfunction "2_2") (pintype "passive"))
      (node (ref "U1") (pin "8") (pinfunction "FB_8") (pintype "input"))
    )
    (net (code "41") (name "Net-(U1-FPWM)") (class "Default")
      (node (ref "C9") (pin "1") (pinfunction "1_1") (pintype "passive"))
      (node (ref "U1") (pin "7") (pinfunction "FPWM_7") (pintype "input"))
      (node (ref "U1") (pin "9") (pinfunction "VCC_9") (pintype "power_in"))
    )
    (net (code "42") (name "Net-(U1-RON)") (class "Default")
      (node (ref "R5") (pin "2") (pinfunction "2_2") (pintype "passive"))
      (node (ref "U1") (pin "5") (pinfunction "RON_5") (pintype "input"))
    )
    (net (code "43") (name "Net-(U1-SS)") (class "Default")
      (node (ref "C7") (pin "1") (pinfunction "1_1") (pintype "passive"))
      (node (ref "U1") (pin "6") (pinfunction "SS_6") (pintype "input"))
    )
    (net (code "44") (name "Net-(U1-SW)") (class "Default")
      (node (ref "C8") (pin "2") (pinfunction "2_2") (pintype "passive"))
      (node (ref "L4") (pin "3") (pinfunction "3_3") (pintype "passive"))
      (node (ref "R8") (pin "1") (pinfunction "1_1") (pintype "passive"))
      (node (ref "U1") (pin "11") (pinfunction "SW_2_11") (pintype "power_in"))
      (node (ref "U1") (pin "12") (pinfunction "SW_12") (pintype "power_in"))
    )
    (net (code "45") (name "Net-(U1-VIN)") (class "Default")
      (node (ref "C2") (pin "1") (pinfunction "1_1") (pintype "passive"))
      (node (ref "C4") (pin "1") (pinfunction "1_1") (pintype "passive"))
      (node (ref "L1") (pin "2") (pinfunction "2_2") (pintype "passive"))
      (node (ref "R2") (pin "2") (pinfunction "2_2") (pintype "passive"))
      (node (ref "R5") (pin "1") (pinfunction "1_1") (pintype "passive"))
      (node (ref "U1") (pin "3") (pinfunction "VIN_3") (pintype "power_in"))
    )
    (net (code "46") (name "Net-(U2-CN)") (class "Default")
      (node (ref "C10") (pin "1") (pinfunction "1_1") (pintype "passive"))
      (node (ref "U2") (pin "18") (pinfunction "CN_18") (pintype "passive"))
    )
    (net (code "47") (name "Net-(U2-CP)") (class "Default")
      (node (ref "C15") (pin "1") (pinfunction "1_1") (pintype "passive"))
      (node (ref "U2") (pin "21") (pinfunction "CP_21") (pintype "passive"))
    )
    (net (code "48") (name "Net-(U2-ENN)") (class "Default")
      (node (ref "C6") (pin "1") (pinfunction "1_1") (pintype "passive"))
      (node (ref "R4") (pin "1") (pinfunction "1_1") (pintype "passive"))
      (node (ref "U2") (pin "10") (pinfunction "ENN_10") (pintype "input"))
      (node (ref "U2") (pin "11") (pinfunction "PSN_11") (pintype "input"))
      (node (ref "U2") (pin "4") (pinfunction "VIN_4") (pintype "power_in"))
      (node (ref "U2") (pin "8") (pinfunction "ENP_8") (pintype "input"))
      (node (ref "U2") (pin "9") (pinfunction "PSP_9") (pintype "input"))
    )
    (net (code "49") (name "Net-(U2-FBN)") (class "Default")
      (node (ref "C12") (pin "1") (pinfunction "1_1") (pintype "passive"))
      (node (ref "R10") (pin "2") (pinfunction "2_2") (pintype "passive"))
      (node (ref "R6") (pin "1") (pinfunction "1_1") (pintype "passive"))
      (node (ref "U2") (pin "16") (pinfunction "FBN_16") (pintype "input"))
    )
    (net (code "50") (name "Net-(U2-FBP)") (class "Default")
      (node (ref "C13") (pin "1") (pinfunction "1_1") (pintype "passive"))
      (node (ref "R11") (pin "2") (pinfunction "2_2") (pintype "passive"))
      (node (ref "R7") (pin "2") (pinfunction "2_2") (pintype "passive"))
      (node (ref "U2") (pin "22") (pinfunction "FBP_22") (pintype "input"))
    )
    (net (code "51") (name "Net-(U2-INN)") (class "Default")
      (node (ref "C3") (pin "1") (pinfunction "1_1") (pintype "passive"))
      (node (ref "C5") (pin "1") (pinfunction "1_1") (pintype "passive"))
      (node (ref "FB1") (pin "2") (pinfunction "2_2") (pintype "passive"))
      (node (ref "L2") (pin "1") (pinfunction "1_1") (pintype "passive"))
      (node (ref "R4") (pin "2") (pinfunction "2_2") (pintype "passive"))
      (node (ref "U2") (pin "5") (pinfunction "INN_2_5") (pintype "power_in"))
      (node (ref "U2") (pin "6") (pinfunction "INN_6") (pintype "power_in"))
    )
    (net (code "52") (name "Net-(U2-VREF)") (class "Default")
      (node (ref "C16") (pin "1") (pinfunction "1_1") (pintype "passive"))
      (node (ref "R6") (pin "2") (pinfunction "2_2") (pintype "passive"))
      (node (ref "U2") (pin "17") (pinfunction "VREF_17") (pintype "output"))
    )
    (net (code "53") (name "Net-(U3-BYPASS)") (class "Default")
      (node (ref "C31") (pin "1") (pinfunction "1_1") (pintype "passive"))
      (node (ref "U3") (pin "4") (pinfunction "BYPASS_4") (pintype "input"))
    )
    (net (code "54") (name "Net-(U3-EN)") (class "Default")
      (node (ref "J3V3") (pin "1") (pinfunction "1_1") (pintype "passive"))
      (node (ref "U3") (pin "1") (pinfunction "VIN_1") (pintype "input"))
      (node (ref "U3") (pin "3") (pinfunction "EN_3") (pintype "input"))
    )
    (net (code "55") (name "unconnected-(U2-BSW-Pad7)") (class "Default")
      (node (ref "U2") (pin "7") (pinfunction "BSW_7") (pintype "output"))
    )
    (net (code "56") (name "unconnected-(U2-NC-Pad20)") (class "Default")
      (node (ref "U2") (pin "20") (pinfunction "NC_20") (pintype "passive"))
    )
    (net (code "57") (name "unconnected-(U2-NC_2-Pad12)") (class "Default")
      (node (ref "U2") (pin "12") (pinfunction "NC_2_12") (pintype "passive"))
    )
  )
)
